# Analog_HC_Overcurrent_MMPQ3904.net
KiCad netlist of a schematic drawn in Altium Designer
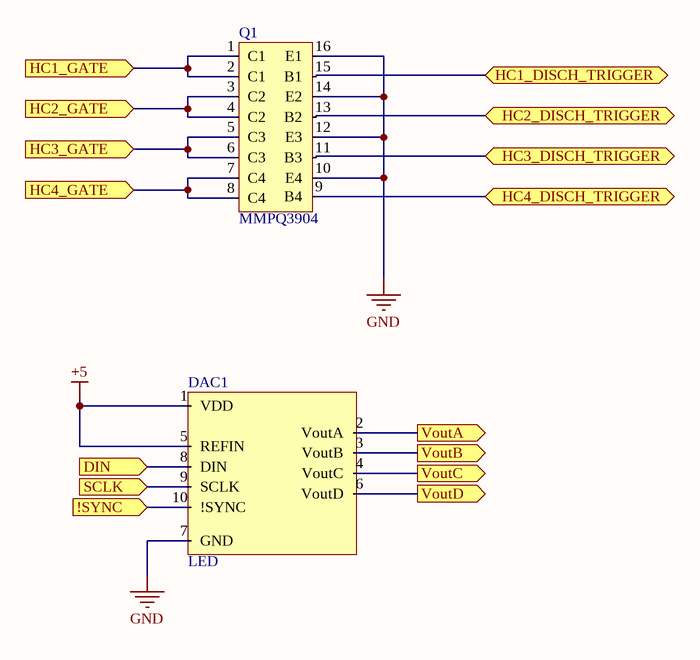
[diagram p0: Analog_HC_Overcurrent_MMPQ3904.SchDoc]

(export (version "E")
  (design (tool "Eeschema 10.0.6"))
  (components
    (comp (ref "DAC1")
      (value "LED")
      (footprint "MSOP10 (RM-10)")
      (description "10bit 4 channel DAC")
      (fields (field (name "MFRPARTNO") "AD5314ARMZ"))
      (libsource (lib "Altium-Lib") (part "AD5314ARMZ"))
    )
    (comp (ref "Q1")
      (value "MMPQ3904")
      (footprint "SOIC-16-NB")
      (fields (field (name "CREATED_BY") "Angel Delgado"))
      (libsource (lib "Altium-Lib") (part "MMPQ3904 NPN General Purpose Amp"))
    )
  )
  (nets
    (net (code "1") (name "+5") (class "Default")
      (node (ref "DAC1") (pin "1") (pinfunction "VDD_1") (pintype "input"))
      (node (ref "DAC1") (pin "5") (pinfunction "REFIN_5") (pintype "input"))
    )
    (net (code "2") (name "/!SYNC") (class "Default")
      (node (ref "DAC1") (pin "10") (pinfunction "!SYNC_10") (pintype "input"))
    )
    (net (code "3") (name "/DIN") (class "Default")
      (node (ref "DAC1") (pin "8") (pinfunction "DIN_8") (pintype "input"))
    )
    (net (code "4") (name "/HC1_DISCH_TRIGGER") (class "Default")
      (node (ref "Q1") (pin "15") (pinfunction "B1_15") (pintype "input"))
    )
    (net (code "5") (name "/HC1_GATE") (class "Default")
      (node (ref "Q1") (pin "1") (pinfunction "C1_1") (pintype "input"))
      (node (ref "Q1") (pin "2") (pinfunction "C1_2") (pintype "input"))
    )
    (net (code "6") (name "/HC2_DISCH_TRIGGER") (class "Default")
      (node (ref "Q1") (pin "13") (pinfunction "B2_13") (pintype "input"))
    )
    (net (code "7") (name "/HC2_GATE") (class "Default")
      (node (ref "Q1") (pin "3") (pinfunction "C2_3") (pintype "input"))
      (node (ref "Q1") (pin "4") (pinfunction "C2_4") (pintype "input"))
    )
    (net (code "8") (name "/HC3_DISCH_TRIGGER") (class "Default")
      (node (ref "Q1") (pin "11") (pinfunction "B3_11") (pintype "input"))
    )
    (net (code "9") (name "/HC3_GATE") (class "Default")
      (node (ref "Q1") (pin "5") (pinfunction "C3_5") (pintype "input"))
      (node (ref "Q1") (pin "6") (pinfunction "C3_6") (pintype "input"))
    )
    (net (code "10") (name "/HC4_DISCH_TRIGGER") (class "Default")
      (node (ref "Q1") (pin "9") (pinfunction "B4_9") (pintype "input"))
    )
    (net (code "11") (name "/HC4_GATE") (class "Default")
      (node (ref "Q1") (pin "7") (pinfunction "C4_7") (pintype "input"))
      (node (ref "Q1") (pin "8") (pinfunction "C4_8") (pintype "input"))
    )
    (net (code "12") (name "/SCLK") (class "Default")
      (node (ref "DAC1") (pin "9") (pinfunction "SCLK_9") (pintype "input"))
    )
    (net (code "13") (name "/VoutA") (class "Default")
      (node (ref "DAC1") (pin "2") (pinfunction "VoutA_2") (pintype "input"))
    )
    (net (code "14") (name "/VoutB") (class "Default")
      (node (ref "DAC1") (pin "3") (pinfunction "VoutB_3") (pintype "input"))
    )
    (net (code "15") (name "/VoutC") (class "Default")
      (node (ref "DAC1") (pin "4") (pinfunction "VoutC_4") (pintype "input"))
    )
    (net (code "16") (name "/VoutD") (class "Default")
      (node (ref "DAC1") (pin "6") (pinfunction "VoutD_6") (pintype "input"))
    )
    (net (code "17") (name "GND") (class "Default")
      (node (ref "DAC1") (pin "7") (pinfunction "GND_7") (pintype "input"))
      (node (ref "Q1") (pin "10") (pinfunction "E4_10") (pintype "input"))
      (node (ref "Q1") (pin "12") (pinfunction "E3_12") (pintype "input"))
      (node (ref "Q1") (pin "14") (pinfunction "E2_14") (pintype "input"))
      (node (ref "Q1") (pin "16") (pinfunction "E1_16") (pintype "input"))
    )
  )
)
